# PHOTOPOLYMER_CURE_LIGHT_V0_0.net
KiCad netlist of a schematic drawn in EasyEDA
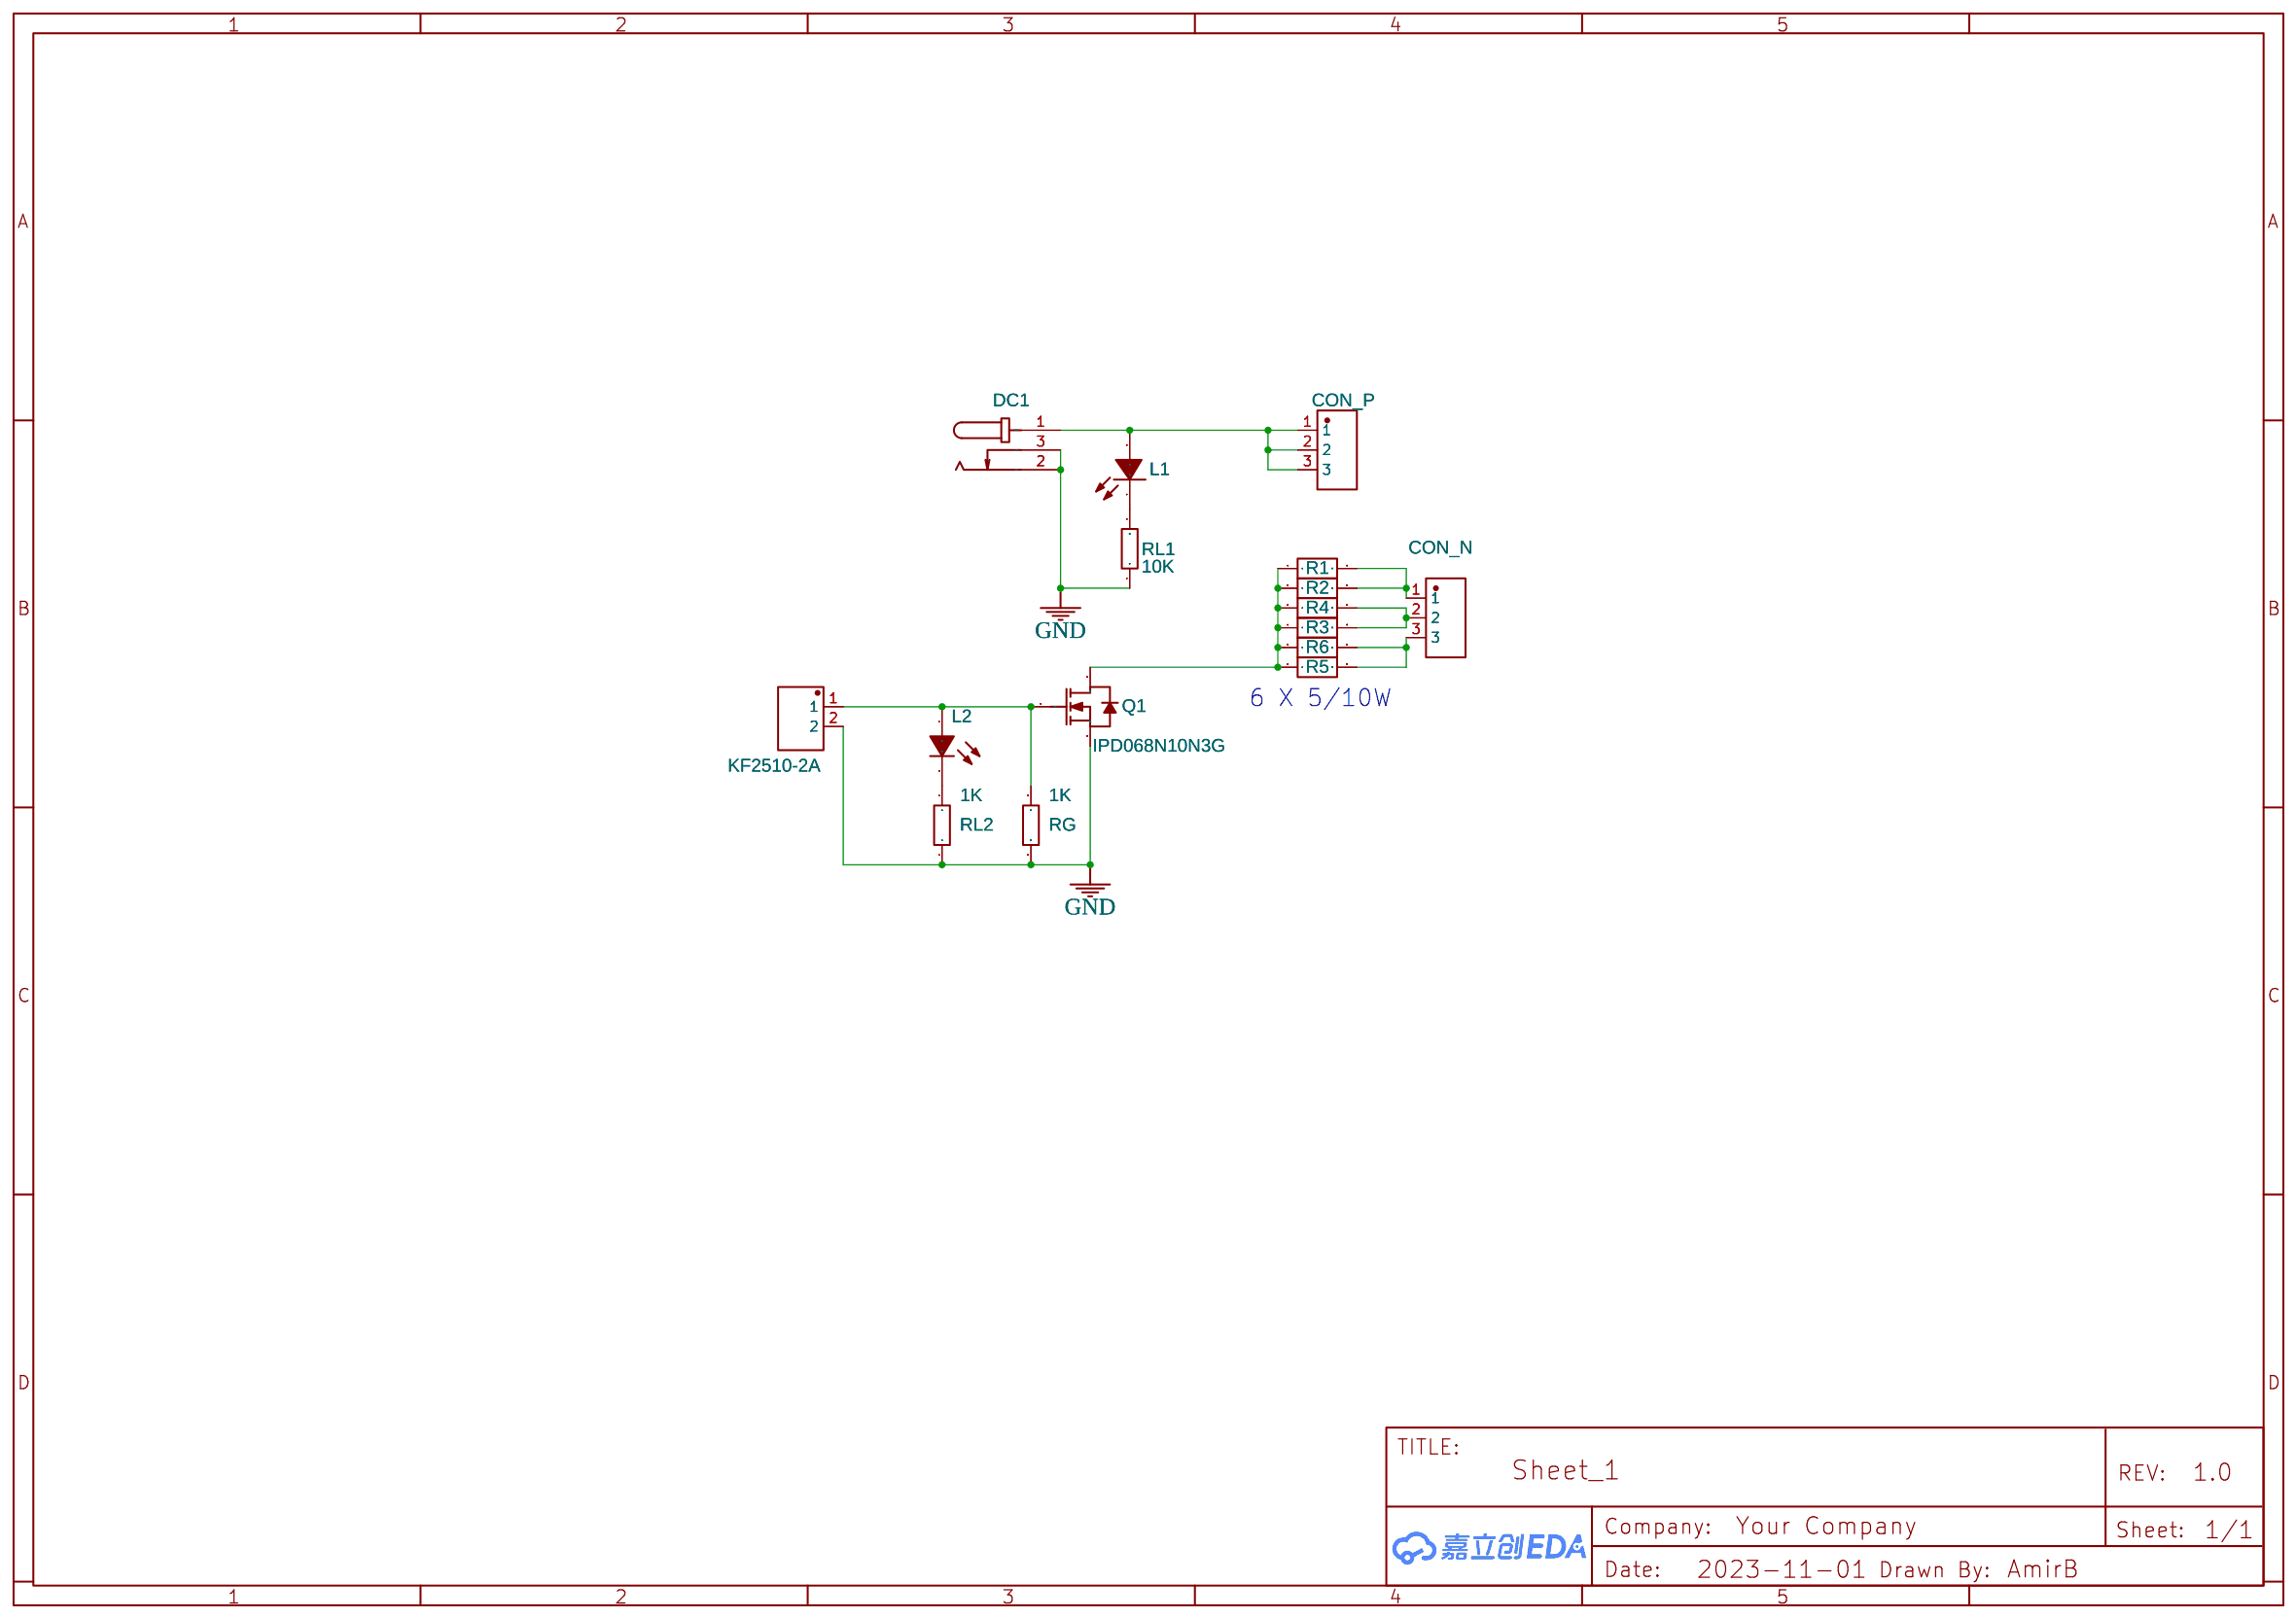
[diagram p0: schematic sheet]

(export (version "E")
  (design (tool "Eeschema 10.0.6"))
  (components
    (comp (ref "CON_N")
      (value "DB126V-5.0-3P")
      (fields
        (field (name "Manufacturer Part") "DB126V-5.0-3P-GN")
        (field (name "Manufacturer") "DIBO(地博电气)")
      )
      (libsource (lib "") (part "DB126V-5.0-3P_1"))
    )
    (comp (ref "CON_P")
      (value "DB126V-5.0-3P")
      (fields
        (field (name "Manufacturer Part") "DB126V-5.0-3P-GN")
        (field (name "Manufacturer") "DIBO(地博电气)")
      )
      (libsource (lib "") (part "DB126V-5.0-3P"))
    )
    (comp (ref "DC1")
      (value "DC")
      (fields
        (field (name "BOM_Manufacturer Part") "DC005-2.0MM")
        (field (name "BOM_Supplier Part") "C111567")
      )
      (libsource (lib "") (part "DC005-2.0MM"))
    )
    (comp (ref "L1")
      (value "KT-0603R")
      (fields (field (name "Manufacturer") "KENTO"))
      (libsource (lib "") (part "KT-0603R"))
    )
    (comp (ref "L2")
      (value "LED")
      (fields
        (field (name "BOM_Manufacturer Part") "19-217/BHC-ZL1M2RY/3T")
        (field (name "BOM_Supplier Part") "C72041")
      )
      (libsource (lib "") (part "19-217/BHC-ZL1M2RY/3T"))
    )
    (comp (ref "Q1")
      (value "IPD068N10N3G")
      (fields (field (name "Manufacturer") "Infineon(英飞凌)"))
      (libsource (lib "") (part "IPD068N10N3G"))
    )
    (comp (ref "R1")
      (value "B12J20RE")
      (fields (field (name "Manufacturer") "Ohmite"))
      (libsource (lib "") (part "B12J20RE"))
    )
    (comp (ref "R2")
      (value "B12J20RE")
      (fields (field (name "Manufacturer") "Ohmite"))
      (libsource (lib "") (part "B12J20RE"))
    )
    (comp (ref "R3")
      (value "B12J20RE")
      (fields (field (name "Manufacturer") "Ohmite"))
      (libsource (lib "") (part "B12J20RE"))
    )
    (comp (ref "R4")
      (value "B12J20RE")
      (fields (field (name "Manufacturer") "Ohmite"))
      (libsource (lib "") (part "B12J20RE"))
    )
    (comp (ref "R5")
      (value "B12J20RE")
      (fields (field (name "Manufacturer") "Ohmite"))
      (libsource (lib "") (part "B12J20RE"))
    )
    (comp (ref "R6")
      (value "B12J20RE")
      (fields (field (name "Manufacturer") "Ohmite"))
      (libsource (lib "") (part "B12J20RE"))
    )
    (comp (ref "RG")
      (value "1K")
      (fields
        (field (name "BOM_Manufacturer Part") "0603WAF1001T5E")
        (field (name "BOM_Supplier Part") "C21190")
      )
      (libsource (lib "") (part "0603WAF1001T5E_1"))
    )
    (comp (ref "RL1")
      (value "10K")
      (fields
        (field (name "BOM_Manufacturer Part") "0603WAF1002T5E")
        (field (name "BOM_Supplier Part") "C25804")
      )
      (libsource (lib "") (part "0603WAF1001T5E"))
    )
    (comp (ref "RL2")
      (value "1K")
      (fields
        (field (name "BOM_Manufacturer Part") "0603WAF1001T5E")
        (field (name "BOM_Supplier Part") "C21190")
      )
      (libsource (lib "") (part "0603WAF1001T5E"))
    )
    (comp (ref "VIN1")
      (value "KF2510-2A")
      (fields (field (name "BOM_Supplier Part") "C27543"))
      (libsource (lib "") (part "KF2510-2A"))
    )
  )
  (nets
    (net (code "1") (name "GND") (class "Default")
      (node (ref "DC1") (pin "2") (pinfunction "2_2") (pintype "unspecified"))
      (node (ref "DC1") (pin "3") (pinfunction "3_3") (pintype "unspecified"))
      (node (ref "Q1") (pin "3") (pinfunction "S_3") (pintype "unspecified"))
      (node (ref "RG") (pin "1") (pinfunction "1_1") (pintype "input"))
      (node (ref "RL1") (pin "1") (pinfunction "1_1") (pintype "input"))
      (node (ref "RL2") (pin "1") (pinfunction "1_1") (pintype "input"))
      (node (ref "VIN1") (pin "2") (pinfunction "2_2") (pintype "unspecified"))
    )
    (net (code "2") (name "Net-(CON_N-Pad1)") (class "Default")
      (node (ref "CON_N") (pin "1") (pinfunction "1_1") (pintype "unspecified"))
      (node (ref "R1") (pin "2") (pinfunction "2_2") (pintype "unspecified"))
      (node (ref "R2") (pin "2") (pinfunction "2_2") (pintype "unspecified"))
    )
    (net (code "3") (name "Net-(CON_N-Pad2)") (class "Default")
      (node (ref "CON_N") (pin "2") (pinfunction "2_2") (pintype "unspecified"))
      (node (ref "R3") (pin "2") (pinfunction "2_2") (pintype "unspecified"))
      (node (ref "R4") (pin "2") (pinfunction "2_2") (pintype "unspecified"))
    )
    (net (code "4") (name "Net-(CON_N-Pad3)") (class "Default")
      (node (ref "CON_N") (pin "3") (pinfunction "3_3") (pintype "unspecified"))
      (node (ref "R5") (pin "2") (pinfunction "2_2") (pintype "unspecified"))
      (node (ref "R6") (pin "2") (pinfunction "2_2") (pintype "unspecified"))
    )
    (net (code "5") (name "Net-(L1-A)") (class "Default")
      (node (ref "CON_P") (pin "1") (pinfunction "1_1") (pintype "unspecified"))
      (node (ref "CON_P") (pin "2") (pinfunction "2_2") (pintype "unspecified"))
      (node (ref "CON_P") (pin "3") (pinfunction "3_3") (pintype "unspecified"))
      (node (ref "DC1") (pin "1") (pinfunction "1_1") (pintype "unspecified"))
      (node (ref "L1") (pin "2") (pinfunction "A_2") (pintype "unspecified"))
    )
    (net (code "6") (name "Net-(L1-K)") (class "Default")
      (node (ref "L1") (pin "1") (pinfunction "K_1") (pintype "unspecified"))
      (node (ref "RL1") (pin "2") (pinfunction "2_2") (pintype "input"))
    )
    (net (code "7") (name "Net-(L2-A)") (class "Default")
      (node (ref "L2") (pin "1") (pinfunction "A_1") (pintype "input"))
      (node (ref "Q1") (pin "1") (pinfunction "G_1") (pintype "unspecified"))
      (node (ref "RG") (pin "2") (pinfunction "2_2") (pintype "input"))
      (node (ref "VIN1") (pin "1") (pinfunction "1_1") (pintype "unspecified"))
    )
    (net (code "8") (name "Net-(L2-C)") (class "Default")
      (node (ref "L2") (pin "2") (pinfunction "C_2") (pintype "input"))
      (node (ref "RL2") (pin "2") (pinfunction "2_2") (pintype "input"))
    )
    (net (code "9") (name "Net-(Q1-D)") (class "Default")
      (node (ref "Q1") (pin "2") (pinfunction "D_2") (pintype "unspecified"))
      (node (ref "R1") (pin "1") (pinfunction "1_1") (pintype "unspecified"))
      (node (ref "R2") (pin "1") (pinfunction "1_1") (pintype "unspecified"))
      (node (ref "R3") (pin "1") (pinfunction "1_1") (pintype "unspecified"))
      (node (ref "R4") (pin "1") (pinfunction "1_1") (pintype "unspecified"))
      (node (ref "R5") (pin "1") (pinfunction "1_1") (pintype "unspecified"))
      (node (ref "R6") (pin "1") (pinfunction "1_1") (pintype "unspecified"))
    )
  )
)
